# TempSensor.net
KiCad netlist of a schematic drawn in EAGLE
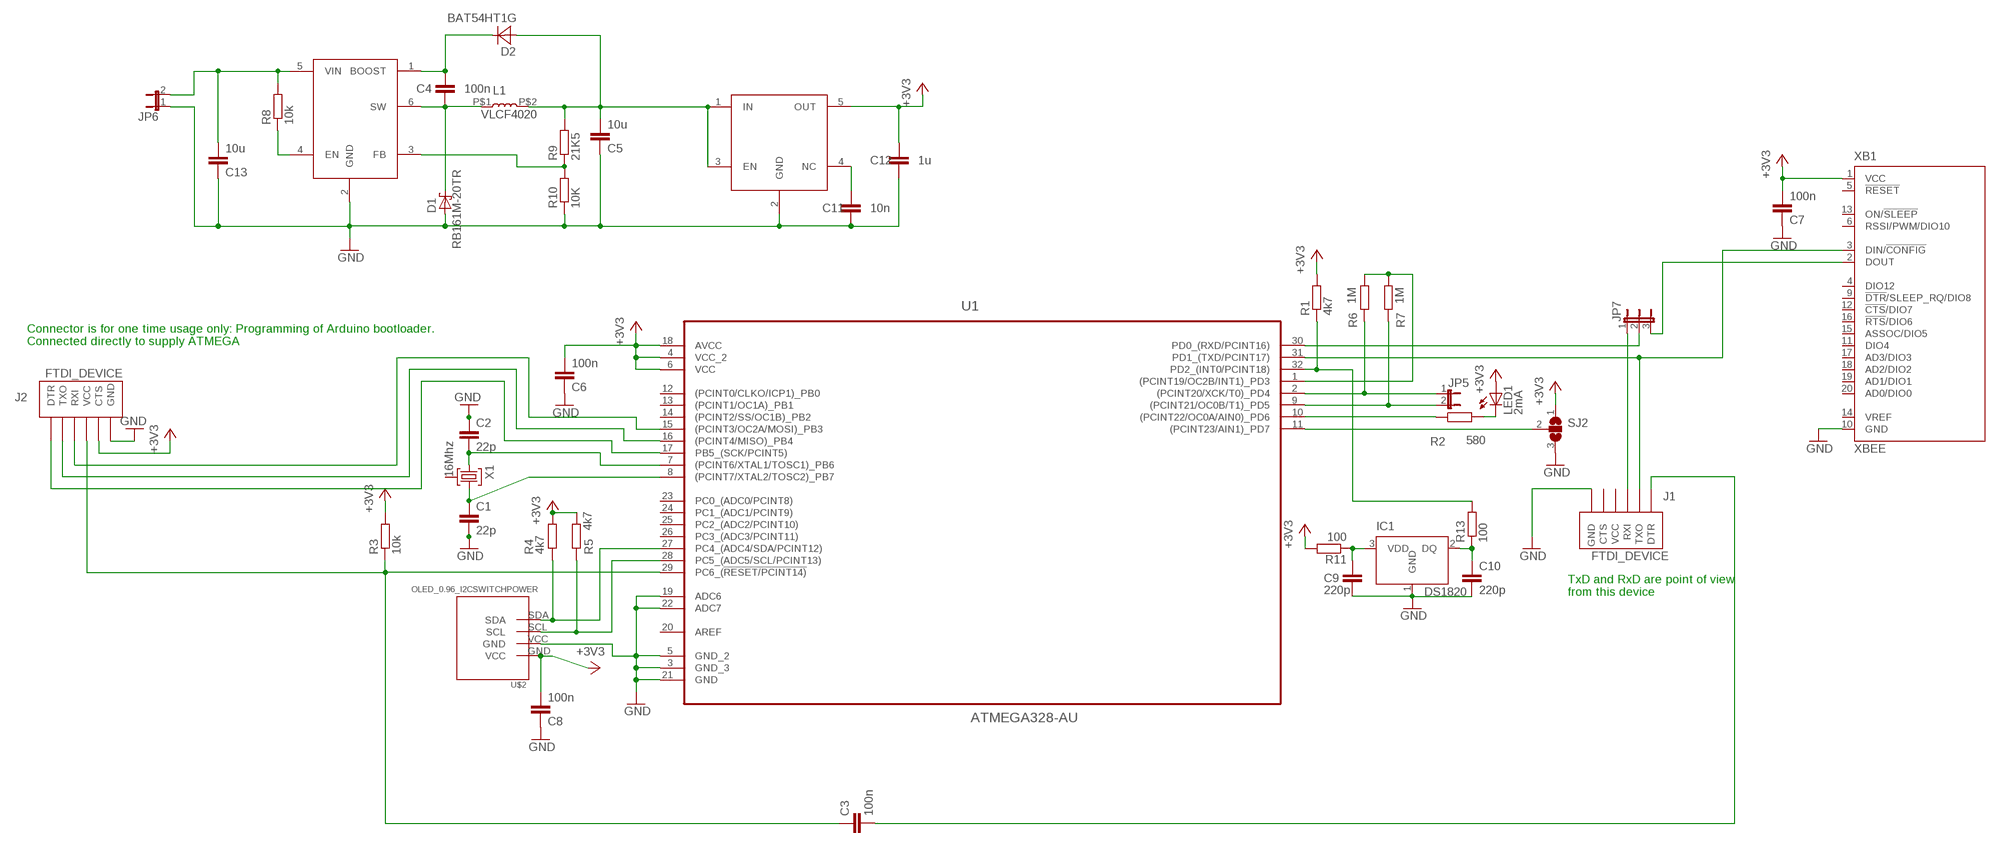
[diagram p0: schematic, sheet 1]

(export (version "E")
  (design (tool "Eeschema 10.0.6"))
  (components
    (comp (ref "C1")
      (value "22p")
      (footprint "eagle-import:C0805")
      (libsource (lib "eagle-import") (part "C-EUC0805"))
    )
    (comp (ref "C2")
      (value "22p")
      (footprint "eagle-import:C0805")
      (libsource (lib "eagle-import") (part "C-EUC0805"))
    )
    (comp (ref "C3")
      (value "100n")
      (footprint "eagle-import:C0805")
      (libsource (lib "eagle-import") (part "C-EUC0805"))
    )
    (comp (ref "C4")
      (value "100n")
      (footprint "eagle-import:C0805")
      (libsource (lib "eagle-import") (part "C-EUC0805"))
    )
    (comp (ref "C5")
      (value "10u")
      (footprint "eagle-import:C0805")
      (libsource (lib "eagle-import") (part "C-EUC0805"))
    )
    (comp (ref "C6")
      (value "100n")
      (footprint "eagle-import:C0805")
      (libsource (lib "eagle-import") (part "C-EUC0805"))
    )
    (comp (ref "C7")
      (value "100n")
      (footprint "eagle-import:C0805")
      (libsource (lib "eagle-import") (part "C-EUC0805"))
    )
    (comp (ref "C8")
      (value "100n")
      (footprint "eagle-import:C0805")
      (libsource (lib "eagle-import") (part "C-EUC0805"))
    )
    (comp (ref "C9")
      (value "220p")
      (footprint "eagle-import:C0805")
      (libsource (lib "eagle-import") (part "C-EUC0805"))
    )
    (comp (ref "C10")
      (value "220p")
      (footprint "eagle-import:C0805")
      (libsource (lib "eagle-import") (part "C-EUC0805"))
    )
    (comp (ref "C11")
      (value "10n")
      (footprint "eagle-import:C0805")
      (libsource (lib "eagle-import") (part "C-EUC0805"))
    )
    (comp (ref "C12")
      (value "1u")
      (footprint "eagle-import:C0805")
      (libsource (lib "eagle-import") (part "C-EUC0805"))
    )
    (comp (ref "C13")
      (value "10u")
      (footprint "eagle-import:C0805")
      (libsource (lib "eagle-import") (part "C-EUC0805"))
    )
    (comp (ref "D1")
      (value "RB161M-20TR")
      (footprint "eagle-import:SOD123")
      (libsource (lib "eagle-import") (part "RB161M-20TR"))
    )
    (comp (ref "D2")
      (value "BAT54HT1G")
      (footprint "eagle-import:SOD323_ST")
      (libsource (lib "eagle-import") (part "BAT54HT1G"))
    )
    (comp (ref "IC1")
      (value "DS1820")
      (footprint "eagle-import:TO-92")
      (libsource (lib "eagle-import") (part "DS1820"))
    )
    (comp (ref "J1")
      (value "FTDI_DEVICE")
      (footprint "eagle-import:FTDI_DEVICE_SIDE")
      (libsource (lib "eagle-import") (part "FTDI_DEVICE"))
    )
    (comp (ref "J2")
      (value "FTDI_DEVICE")
      (footprint "eagle-import:FTDI_DEVICE_SIDE")
      (libsource (lib "eagle-import") (part "FTDI_DEVICE"))
    )
    (comp (ref "JP5")
      (value "JP1E")
      (footprint "eagle-import:JP1")
      (libsource (lib "eagle-import") (part "JP1E"))
    )
    (comp (ref "JP6")
      (value "JP1E")
      (footprint "eagle-import:JP1")
      (libsource (lib "eagle-import") (part "JP1E"))
    )
    (comp (ref "JP7")
      (value "JP2E")
      (footprint "eagle-import:JP2")
      (libsource (lib "eagle-import") (part "JP2E"))
    )
    (comp (ref "L1")
      (value "VLCF4020")
      (footprint "eagle-import:VLCF4020")
      (libsource (lib "eagle-import") (part "VLCF4020"))
    )
    (comp (ref "LED1")
      (value "2mA")
      (footprint "eagle-import:LED3MM")
      (libsource (lib "eagle-import") (part "LED3MM"))
    )
    (comp (ref "R1")
      (value "4k7")
      (footprint "eagle-import:R0805")
      (libsource (lib "eagle-import") (part "R-EU_R0805"))
    )
    (comp (ref "R2")
      (value "580")
      (footprint "eagle-import:R0603")
      (libsource (lib "eagle-import") (part "R-EU_R0603"))
    )
    (comp (ref "R3")
      (value "10k")
      (footprint "eagle-import:R0805")
      (libsource (lib "eagle-import") (part "R-EU_R0805"))
    )
    (comp (ref "R4")
      (value "4k7")
      (footprint "eagle-import:R0805")
      (libsource (lib "eagle-import") (part "R-EU_R0805"))
    )
    (comp (ref "R5")
      (value "4k7")
      (footprint "eagle-import:R0805")
      (libsource (lib "eagle-import") (part "R-EU_R0805"))
    )
    (comp (ref "R6")
      (value "1M")
      (footprint "eagle-import:R0805")
      (libsource (lib "eagle-import") (part "R-EU_R0805"))
    )
    (comp (ref "R7")
      (value "1M")
      (footprint "eagle-import:R0805")
      (libsource (lib "eagle-import") (part "R-EU_R0805"))
    )
    (comp (ref "R8")
      (value "10k")
      (footprint "eagle-import:R0805")
      (libsource (lib "eagle-import") (part "R-EU_R0805"))
    )
    (comp (ref "R9")
      (value "21K5")
      (footprint "eagle-import:R0805")
      (libsource (lib "eagle-import") (part "R-EU_R0805"))
    )
    (comp (ref "R10")
      (value "10K")
      (footprint "eagle-import:R0805")
      (libsource (lib "eagle-import") (part "R-EU_R0805"))
    )
    (comp (ref "R11")
      (value "100")
      (footprint "eagle-import:R0805")
      (libsource (lib "eagle-import") (part "R-EU_R0805"))
    )
    (comp (ref "R13")
      (value "100")
      (footprint "eagle-import:R0805")
      (libsource (lib "eagle-import") (part "R-EU_R0805"))
    )
    (comp (ref "SJ2")
      (value "SJ2W")
      (footprint "eagle-import:SJ_2")
      (libsource (lib "eagle-import") (part "SJ2W"))
    )
    (comp (ref "U$2")
      (value "OLED_0.96_I2CSWITCHPOWER")
      (footprint "eagle-import:OLED_0.96_I2C")
      (libsource (lib "eagle-import") (part "OLED_0.96_I2CSWITCHPOWER"))
    )
    (comp (ref "U1")
      (value "ATMEGA328-AU")
      (footprint "eagle-import:QFP80P900X900X120-32N")
      (fields (field (name "MF") "ATMEL"))
      (libsource (lib "eagle-import") (part "ATMEGA328-AU"))
    )
    (comp (ref "U2")
      (value "LM2736X")
      (footprint "eagle-import:SOT23-6L")
      (libsource (lib "eagle-import") (part "LM2736X"))
    )
    (comp (ref "U3")
      (value "XC6210")
      (footprint "eagle-import:SOT23-5")
      (libsource (lib "eagle-import") (part "XC6210"))
    )
    (comp (ref "X1")
      (value "16Mhz")
      (footprint "eagle-import:HC49-3L")
      (fields (field (name "MF") "IQD FREQUENCY PRODUCTS") (field (name "MPN") "LFXTAL003240"))
      (libsource (lib "eagle-import") (part "HC49-HC49-3L"))
    )
    (comp (ref "XB1")
      (value "XBEE")
      (footprint "eagle-import:XBEE")
      (fields (field (name "MPN") "XBP24-Z7UIT-004"))
      (libsource (lib "eagle-import") (part "XBEE"))
    )
  )
  (nets
    (net (code "1") (name "+3V3") (class "Default")
      (node (ref "C12") (pin "2") (pinfunction "2_2") (pintype "passive"))
      (node (ref "C6") (pin "2") (pinfunction "2_2") (pintype "passive"))
      (node (ref "C7") (pin "2") (pinfunction "2_2") (pintype "passive"))
      (node (ref "C8") (pin "2") (pinfunction "2_2") (pintype "passive"))
      (node (ref "J2") (pin "P$5") (pinfunction "CTS_P$5") (pintype "bidirectional"))
      (node (ref "LED1") (pin "A") (pinfunction "A_A") (pintype "passive"))
      (node (ref "R1") (pin "2") (pinfunction "2_2") (pintype "passive"))
      (node (ref "R11") (pin "2") (pinfunction "2_2") (pintype "passive"))
      (node (ref "R3") (pin "2") (pinfunction "2_2") (pintype "passive"))
      (node (ref "R4") (pin "2") (pinfunction "2_2") (pintype "passive"))
      (node (ref "R5") (pin "2") (pinfunction "2_2") (pintype "passive"))
      (node (ref "SJ2") (pin "1") (pinfunction "1_1") (pintype "passive"))
      (node (ref "U$2") (pin "GND") (pinfunction "VCC_GND") (pintype "bidirectional"))
      (node (ref "U1") (pin "18") (pinfunction "AVCC_18") (pintype "power_in"))
      (node (ref "U1") (pin "4") (pinfunction "VCC_2_4") (pintype "power_in"))
      (node (ref "U1") (pin "6") (pinfunction "VCC_6") (pintype "power_in"))
      (node (ref "U3") (pin "5") (pinfunction "OUT_5") (pintype "bidirectional"))
      (node (ref "XB1") (pin "1") (pinfunction "VCC_1") (pintype "power_in"))
    )
    (net (code "2") (name "GND") (class "Default")
      (node (ref "C1") (pin "2") (pinfunction "2_2") (pintype "passive"))
      (node (ref "C10") (pin "1") (pinfunction "1_1") (pintype "passive"))
      (node (ref "C11") (pin "1") (pinfunction "1_1") (pintype "passive"))
      (node (ref "C12") (pin "1") (pinfunction "1_1") (pintype "passive"))
      (node (ref "C13") (pin "1") (pinfunction "1_1") (pintype "passive"))
      (node (ref "C2") (pin "1") (pinfunction "1_1") (pintype "passive"))
      (node (ref "C5") (pin "1") (pinfunction "1_1") (pintype "passive"))
      (node (ref "C6") (pin "1") (pinfunction "1_1") (pintype "passive"))
      (node (ref "C7") (pin "1") (pinfunction "1_1") (pintype "passive"))
      (node (ref "C8") (pin "1") (pinfunction "1_1") (pintype "passive"))
      (node (ref "C9") (pin "1") (pinfunction "1_1") (pintype "passive"))
      (node (ref "D1") (pin "A") (pinfunction "A_A") (pintype "passive"))
      (node (ref "IC1") (pin "1") (pinfunction "GND_1") (pintype "power_in"))
      (node (ref "J1") (pin "P$6") (pinfunction "GND_P$6") (pintype "bidirectional"))
      (node (ref "J2") (pin "P$6") (pinfunction "GND_P$6") (pintype "bidirectional"))
      (node (ref "JP6") (pin "1") (pinfunction "1_1") (pintype "passive"))
      (node (ref "R10") (pin "1") (pinfunction "1_1") (pintype "passive"))
      (node (ref "SJ2") (pin "3") (pinfunction "3_3") (pintype "passive"))
      (node (ref "U$2") (pin "VCC") (pinfunction "GND_VCC") (pintype "bidirectional"))
      (node (ref "U1") (pin "19") (pinfunction "ADC6_19") (pintype "input"))
      (node (ref "U1") (pin "21") (pinfunction "GND_21") (pintype "passive"))
      (node (ref "U1") (pin "22") (pinfunction "ADC7_22") (pintype "input"))
      (node (ref "U1") (pin "3") (pinfunction "GND_3_3") (pintype "passive"))
      (node (ref "U1") (pin "5") (pinfunction "GND_2_5") (pintype "passive"))
      (node (ref "U2") (pin "2") (pinfunction "GND_2") (pintype "bidirectional"))
      (node (ref "U3") (pin "2") (pinfunction "GND_2") (pintype "bidirectional"))
      (node (ref "XB1") (pin "10") (pinfunction "GND_10") (pintype "power_in"))
    )
    (net (code "3") (name "Net-(IC1-DQ)") (class "Default")
      (node (ref "C10") (pin "2") (pinfunction "2_2") (pintype "passive"))
      (node (ref "IC1") (pin "2") (pinfunction "DQ_2") (pintype "output"))
      (node (ref "R13") (pin "1") (pinfunction "1_1") (pintype "passive"))
    )
    (net (code "4") (name "Net-(IC1-VDD)") (class "Default")
      (node (ref "C9") (pin "2") (pinfunction "2_2") (pintype "passive"))
      (node (ref "IC1") (pin "3") (pinfunction "VDD_3") (pintype "input"))
      (node (ref "R11") (pin "1") (pinfunction "1_1") (pintype "passive"))
    )
    (net (code "5") (name "Net-(J1-DTR)") (class "Default")
      (node (ref "C3") (pin "2") (pinfunction "2_2") (pintype "passive"))
      (node (ref "J1") (pin "P$1") (pinfunction "DTR_P$1") (pintype "bidirectional"))
    )
    (net (code "6") (name "Net-(J1-RXI)") (class "Default")
      (node (ref "J1") (pin "P$3") (pinfunction "RXI_P$3") (pintype "bidirectional"))
      (node (ref "JP7") (pin "1") (pinfunction "1_1") (pintype "passive"))
    )
    (net (code "7") (name "Net-(J1-TXO)") (class "Default")
      (node (ref "J1") (pin "P$2") (pinfunction "TXO_P$2") (pintype "bidirectional"))
      (node (ref "U1") (pin "31") (pinfunction "PD1_(TXD/PCINT17)_31") (pintype "bidirectional"))
      (node (ref "XB1") (pin "3") (pinfunction "DIN/~{CONFIG}_3") (pintype "input"))
    )
    (net (code "8") (name "Net-(J2-DTR)") (class "Default")
      (node (ref "J2") (pin "P$1") (pinfunction "DTR_P$1") (pintype "bidirectional"))
      (node (ref "U1") (pin "17") (pinfunction "PB5_(SCK/PCINT5)_17") (pintype "bidirectional"))
    )
    (net (code "9") (name "Net-(J2-RXI)") (class "Default")
      (node (ref "J2") (pin "P$3") (pinfunction "RXI_P$3") (pintype "bidirectional"))
      (node (ref "U1") (pin "15") (pinfunction "(PCINT3/OC2A/MOSI)_PB3_15") (pintype "bidirectional"))
    )
    (net (code "10") (name "Net-(J2-TXO)") (class "Default")
      (node (ref "J2") (pin "P$2") (pinfunction "TXO_P$2") (pintype "bidirectional"))
      (node (ref "U1") (pin "16") (pinfunction "(PCINT4/MISO)_PB4_16") (pintype "bidirectional"))
    )
    (net (code "11") (name "Net-(J2-VCC)") (class "Default")
      (node (ref "C3") (pin "1") (pinfunction "1_1") (pintype "passive"))
      (node (ref "J2") (pin "P$4") (pinfunction "VCC_P$4") (pintype "bidirectional"))
      (node (ref "R3") (pin "1") (pinfunction "1_1") (pintype "passive"))
      (node (ref "U1") (pin "29") (pinfunction "PC6_(~{RESET/PCINT14})_29") (pintype "bidirectional"))
    )
    (net (code "12") (name "Net-(L1-1)") (class "Default")
      (node (ref "C4") (pin "1") (pinfunction "1_1") (pintype "passive"))
      (node (ref "D1") (pin "C") (pinfunction "C_C") (pintype "passive"))
      (node (ref "L1") (pin "P$1") (pinfunction "1_P$1") (pintype "passive"))
      (node (ref "U2") (pin "6") (pinfunction "SW_6") (pintype "bidirectional"))
    )
    (net (code "13") (name "Net-(L1-2)") (class "Default")
      (node (ref "C5") (pin "2") (pinfunction "2_2") (pintype "passive"))
      (node (ref "D2") (pin "A") (pinfunction "A_A") (pintype "passive"))
      (node (ref "L1") (pin "P$2") (pinfunction "2_P$2") (pintype "passive"))
      (node (ref "R9") (pin "2") (pinfunction "2_2") (pintype "passive"))
      (node (ref "U3") (pin "1") (pinfunction "IN_1") (pintype "bidirectional"))
      (node (ref "U3") (pin "3") (pinfunction "EN_3") (pintype "bidirectional"))
    )
    (net (code "14") (name "Net-(LED1-C)") (class "Default")
      (node (ref "LED1") (pin "K") (pinfunction "C_K") (pintype "passive"))
      (node (ref "R2") (pin "2") (pinfunction "2_2") (pintype "passive"))
    )
    (net (code "15") (name "Net-(U1-(PCINT6{slash}XTAL1{slash}TOSC1)_PB6)") (class "Default")
      (node (ref "C2") (pin "2") (pinfunction "2_2") (pintype "passive"))
      (node (ref "U1") (pin "7") (pinfunction "(PCINT6/XTAL1/TOSC1)_PB6_7") (pintype "bidirectional"))
      (node (ref "X1") (pin "1") (pinfunction "1_1") (pintype "passive"))
    )
    (net (code "16") (name "Net-(U1-(PCINT7{slash}XTAL2{slash}TOSC2)_PB7)") (class "Default")
      (node (ref "C1") (pin "1") (pinfunction "1_1") (pintype "passive"))
      (node (ref "U1") (pin "8") (pinfunction "(PCINT7/XTAL2/TOSC2)_PB7_8") (pintype "bidirectional"))
      (node (ref "X1") (pin "3") (pinfunction "3_3") (pintype "passive"))
    )
    (net (code "17") (name "Net-(U1-(PCINT19{slash}OC2B{slash}INT1)_PD3)") (class "Default")
      (node (ref "R6") (pin "2") (pinfunction "2_2") (pintype "passive"))
      (node (ref "R7") (pin "2") (pinfunction "2_2") (pintype "passive"))
      (node (ref "U1") (pin "1") (pinfunction "(PCINT19/OC2B/INT1)_PD3_1") (pintype "bidirectional"))
    )
    (net (code "18") (name "Net-(U1-(PCINT20{slash}XCK{slash}T0)_PD4)") (class "Default")
      (node (ref "JP5") (pin "1") (pinfunction "1_1") (pintype "passive"))
      (node (ref "R6") (pin "1") (pinfunction "1_1") (pintype "passive"))
      (node (ref "U1") (pin "2") (pinfunction "(PCINT20/XCK/T0)_PD4_2") (pintype "bidirectional"))
    )
    (net (code "19") (name "Net-(U1-(PCINT21{slash}OC0B{slash}T1)_PD5)") (class "Default")
      (node (ref "JP5") (pin "2") (pinfunction "2_2") (pintype "passive"))
      (node (ref "R7") (pin "1") (pinfunction "1_1") (pintype "passive"))
      (node (ref "U1") (pin "9") (pinfunction "(PCINT21/OC0B/T1)_PD5_9") (pintype "bidirectional"))
    )
    (net (code "20") (name "Net-(U1-(PCINT22{slash}OC0A{slash}AIN0)_PD6)") (class "Default")
      (node (ref "R2") (pin "1") (pinfunction "1_1") (pintype "passive"))
      (node (ref "U1") (pin "10") (pinfunction "(PCINT22/OC0A/AIN0)_PD6_10") (pintype "bidirectional"))
    )
    (net (code "21") (name "Net-(U1-(PCINT23{slash}AIN1)_PD7)") (class "Default")
      (node (ref "SJ2") (pin "2") (pinfunction "2_2") (pintype "passive"))
      (node (ref "U1") (pin "11") (pinfunction "(PCINT23/AIN1)_PD7_11") (pintype "bidirectional"))
    )
    (net (code "22") (name "Net-(U1-PC4_(ADC4{slash}SDA{slash}PCINT12))") (class "Default")
      (node (ref "R4") (pin "1") (pinfunction "1_1") (pintype "passive"))
      (node (ref "U$2") (pin "SDA") (pinfunction "SDA_SDA") (pintype "bidirectional"))
      (node (ref "U1") (pin "27") (pinfunction "PC4_(ADC4/SDA/PCINT12)_27") (pintype "bidirectional"))
    )
    (net (code "23") (name "Net-(U1-PC5_(ADC5{slash}SCL{slash}PCINT13))") (class "Default")
      (node (ref "R5") (pin "1") (pinfunction "1_1") (pintype "passive"))
      (node (ref "U$2") (pin "SCL") (pinfunction "SCL_SCL") (pintype "bidirectional"))
      (node (ref "U1") (pin "28") (pinfunction "PC5_(ADC5/SCL/PCINT13)_28") (pintype "bidirectional"))
    )
    (net (code "24") (name "Net-(U1-PD0_(RXD{slash}PCINT16))") (class "Default")
      (node (ref "JP7") (pin "2") (pinfunction "2_2") (pintype "passive"))
      (node (ref "U1") (pin "30") (pinfunction "PD0_(RXD/PCINT16)_30") (pintype "bidirectional"))
    )
    (net (code "25") (name "Net-(U1-PD2_(INT0{slash}PCINT18))") (class "Default")
      (node (ref "R1") (pin "1") (pinfunction "1_1") (pintype "passive"))
      (node (ref "R13") (pin "2") (pinfunction "2_2") (pintype "passive"))
      (node (ref "U1") (pin "32") (pinfunction "PD2_(INT0/PCINT18)_32") (pintype "bidirectional"))
    )
    (net (code "26") (name "Net-(U2-BOOST)") (class "Default")
      (node (ref "C4") (pin "2") (pinfunction "2_2") (pintype "passive"))
      (node (ref "D2") (pin "C") (pinfunction "C_C") (pintype "passive"))
      (node (ref "U2") (pin "1") (pinfunction "BOOST_1") (pintype "bidirectional"))
    )
    (net (code "27") (name "Net-(U2-EN)") (class "Default")
      (node (ref "R8") (pin "1") (pinfunction "1_1") (pintype "passive"))
      (node (ref "U2") (pin "4") (pinfunction "EN_4") (pintype "bidirectional"))
    )
    (net (code "28") (name "Net-(U2-FB)") (class "Default")
      (node (ref "R10") (pin "2") (pinfunction "2_2") (pintype "passive"))
      (node (ref "R9") (pin "1") (pinfunction "1_1") (pintype "passive"))
      (node (ref "U2") (pin "3") (pinfunction "FB_3") (pintype "bidirectional"))
    )
    (net (code "29") (name "Net-(U2-VIN)") (class "Default")
      (node (ref "C13") (pin "2") (pinfunction "2_2") (pintype "passive"))
      (node (ref "JP6") (pin "2") (pinfunction "2_2") (pintype "passive"))
      (node (ref "R8") (pin "2") (pinfunction "2_2") (pintype "passive"))
      (node (ref "U2") (pin "5") (pinfunction "VIN_5") (pintype "bidirectional"))
    )
    (net (code "30") (name "Net-(U3-NC)") (class "Default")
      (node (ref "C11") (pin "2") (pinfunction "2_2") (pintype "passive"))
      (node (ref "U3") (pin "4") (pinfunction "NC_4") (pintype "bidirectional"))
    )
    (net (code "31") (name "Net-(XB1-DOUT)") (class "Default")
      (node (ref "JP7") (pin "3") (pinfunction "3_3") (pintype "passive"))
      (node (ref "XB1") (pin "2") (pinfunction "DOUT_2") (pintype "output"))
    )
    (net (code "32") (name "unconnected-(J1-CTS-PadP$5)") (class "Default")
      (node (ref "J1") (pin "P$5") (pinfunction "CTS_P$5") (pintype "bidirectional"))
    )
    (net (code "33") (name "unconnected-(J1-VCC-PadP$4)") (class "Default")
      (node (ref "J1") (pin "P$4") (pinfunction "VCC_P$4") (pintype "bidirectional"))
    )
    (net (code "34") (name "unconnected-(U1-(PCINT0{slash}CLKO{slash}ICP1)_PB0-Pad12)") (class "Default")
      (node (ref "U1") (pin "12") (pinfunction "(PCINT0/CLKO/ICP1)_PB0_12") (pintype "bidirectional"))
    )
    (net (code "35") (name "unconnected-(U1-(PCINT1{slash}OC1A)_PB1-Pad13)") (class "Default")
      (node (ref "U1") (pin "13") (pinfunction "(PCINT1/OC1A)_PB1_13") (pintype "bidirectional"))
    )
    (net (code "36") (name "unconnected-(U1-(PCINT2{slash}SS{slash}OC1B)_PB2-Pad14)") (class "Default")
      (node (ref "U1") (pin "14") (pinfunction "(PCINT2/SS/OC1B)_PB2_14") (pintype "bidirectional"))
    )
    (net (code "37") (name "unconnected-(U1-AREF-Pad20)") (class "Default")
      (node (ref "U1") (pin "20") (pinfunction "AREF_20") (pintype "passive"))
    )
    (net (code "38") (name "unconnected-(U1-PC0_(ADC0{slash}PCINT8)-Pad23)") (class "Default")
      (node (ref "U1") (pin "23") (pinfunction "PC0_(ADC0/PCINT8)_23") (pintype "bidirectional"))
    )
    (net (code "39") (name "unconnected-(U1-PC1_(ADC1{slash}PCINT9)-Pad24)") (class "Default")
      (node (ref "U1") (pin "24") (pinfunction "PC1_(ADC1/PCINT9)_24") (pintype "bidirectional"))
    )
    (net (code "40") (name "unconnected-(U1-PC2_(ADC2{slash}PCINT10)-Pad25)") (class "Default")
      (node (ref "U1") (pin "25") (pinfunction "PC2_(ADC2/PCINT10)_25") (pintype "bidirectional"))
    )
    (net (code "41") (name "unconnected-(U1-PC3_(ADC3{slash}PCINT11)-Pad26)") (class "Default")
      (node (ref "U1") (pin "26") (pinfunction "PC3_(ADC3/PCINT11)_26") (pintype "bidirectional"))
    )
    (net (code "42") (name "unconnected-(X1-Pad2)") (class "Default")
      (node (ref "X1") (pin "2") (pinfunction "2_2") (pintype "passive"))
    )
    (net (code "43") (name "unconnected-(XB1-AD0{slash}DIO0-Pad20)") (class "Default")
      (node (ref "XB1") (pin "20") (pinfunction "AD0/DIO0_20") (pintype "bidirectional"))
    )
    (net (code "44") (name "unconnected-(XB1-AD1{slash}DIO1-Pad19)") (class "Default")
      (node (ref "XB1") (pin "19") (pinfunction "AD1/DIO1_19") (pintype "bidirectional"))
    )
    (net (code "45") (name "unconnected-(XB1-AD2{slash}DIO2-Pad18)") (class "Default")
      (node (ref "XB1") (pin "18") (pinfunction "AD2/DIO2_18") (pintype "bidirectional"))
    )
    (net (code "46") (name "unconnected-(XB1-AD3{slash}DIO3-Pad17)") (class "Default")
      (node (ref "XB1") (pin "17") (pinfunction "AD3/DIO3_17") (pintype "bidirectional"))
    )
    (net (code "47") (name "unconnected-(XB1-ASSOC{slash}DIO5-Pad15)") (class "Default")
      (node (ref "XB1") (pin "15") (pinfunction "ASSOC/DIO5_15") (pintype "bidirectional"))
    )
    (net (code "48") (name "unconnected-(XB1-DIO4-Pad11)") (class "Default")
      (node (ref "XB1") (pin "11") (pinfunction "DIO4_11") (pintype "bidirectional"))
    )
    (net (code "49") (name "unconnected-(XB1-DIO12-Pad4)") (class "Default")
      (node (ref "XB1") (pin "4") (pinfunction "DIO12_4") (pintype "bidirectional"))
    )
    (net (code "50") (name "unconnected-(XB1-ON{slash}~{SLEEP}-Pad13)") (class "Default")
      (node (ref "XB1") (pin "13") (pinfunction "ON/~{SLEEP}_13") (pintype "output"))
    )
    (net (code "51") (name "unconnected-(XB1-RSSI{slash}PWM{slash}DIO10-Pad6)") (class "Default")
      (node (ref "XB1") (pin "6") (pinfunction "RSSI/PWM/DIO10_6") (pintype "output"))
    )
    (net (code "52") (name "unconnected-(XB1-VREF-Pad14)") (class "Default")
      (node (ref "XB1") (pin "14") (pinfunction "VREF_14") (pintype "input"))
    )
    (net (code "53") (name "unconnected-(XB1-~{CTS}{slash}DIO7-Pad12)") (class "Default")
      (node (ref "XB1") (pin "12") (pinfunction "~{CTS}/DIO7_12") (pintype "bidirectional"))
    )
    (net (code "54") (name "unconnected-(XB1-~{DTR}{slash}SLEEP_RQ{slash}DIO8-Pad9)") (class "Default")
      (node (ref "XB1") (pin "9") (pinfunction "~{DTR}/SLEEP_RQ/DIO8_9") (pintype "bidirectional"))
    )
    (net (code "55") (name "unconnected-(XB1-~{RESET}-Pad5)") (class "Default")
      (node (ref "XB1") (pin "5") (pinfunction "~{RESET}_5") (pintype "input"))
    )
    (net (code "56") (name "unconnected-(XB1-~{RTS}{slash}DIO6-Pad16)") (class "Default")
      (node (ref "XB1") (pin "16") (pinfunction "~{RTS}/DIO6_16") (pintype "bidirectional"))
    )
  )
)
